# Nixie.net
KiCad netlist of a schematic drawn in EAGLE
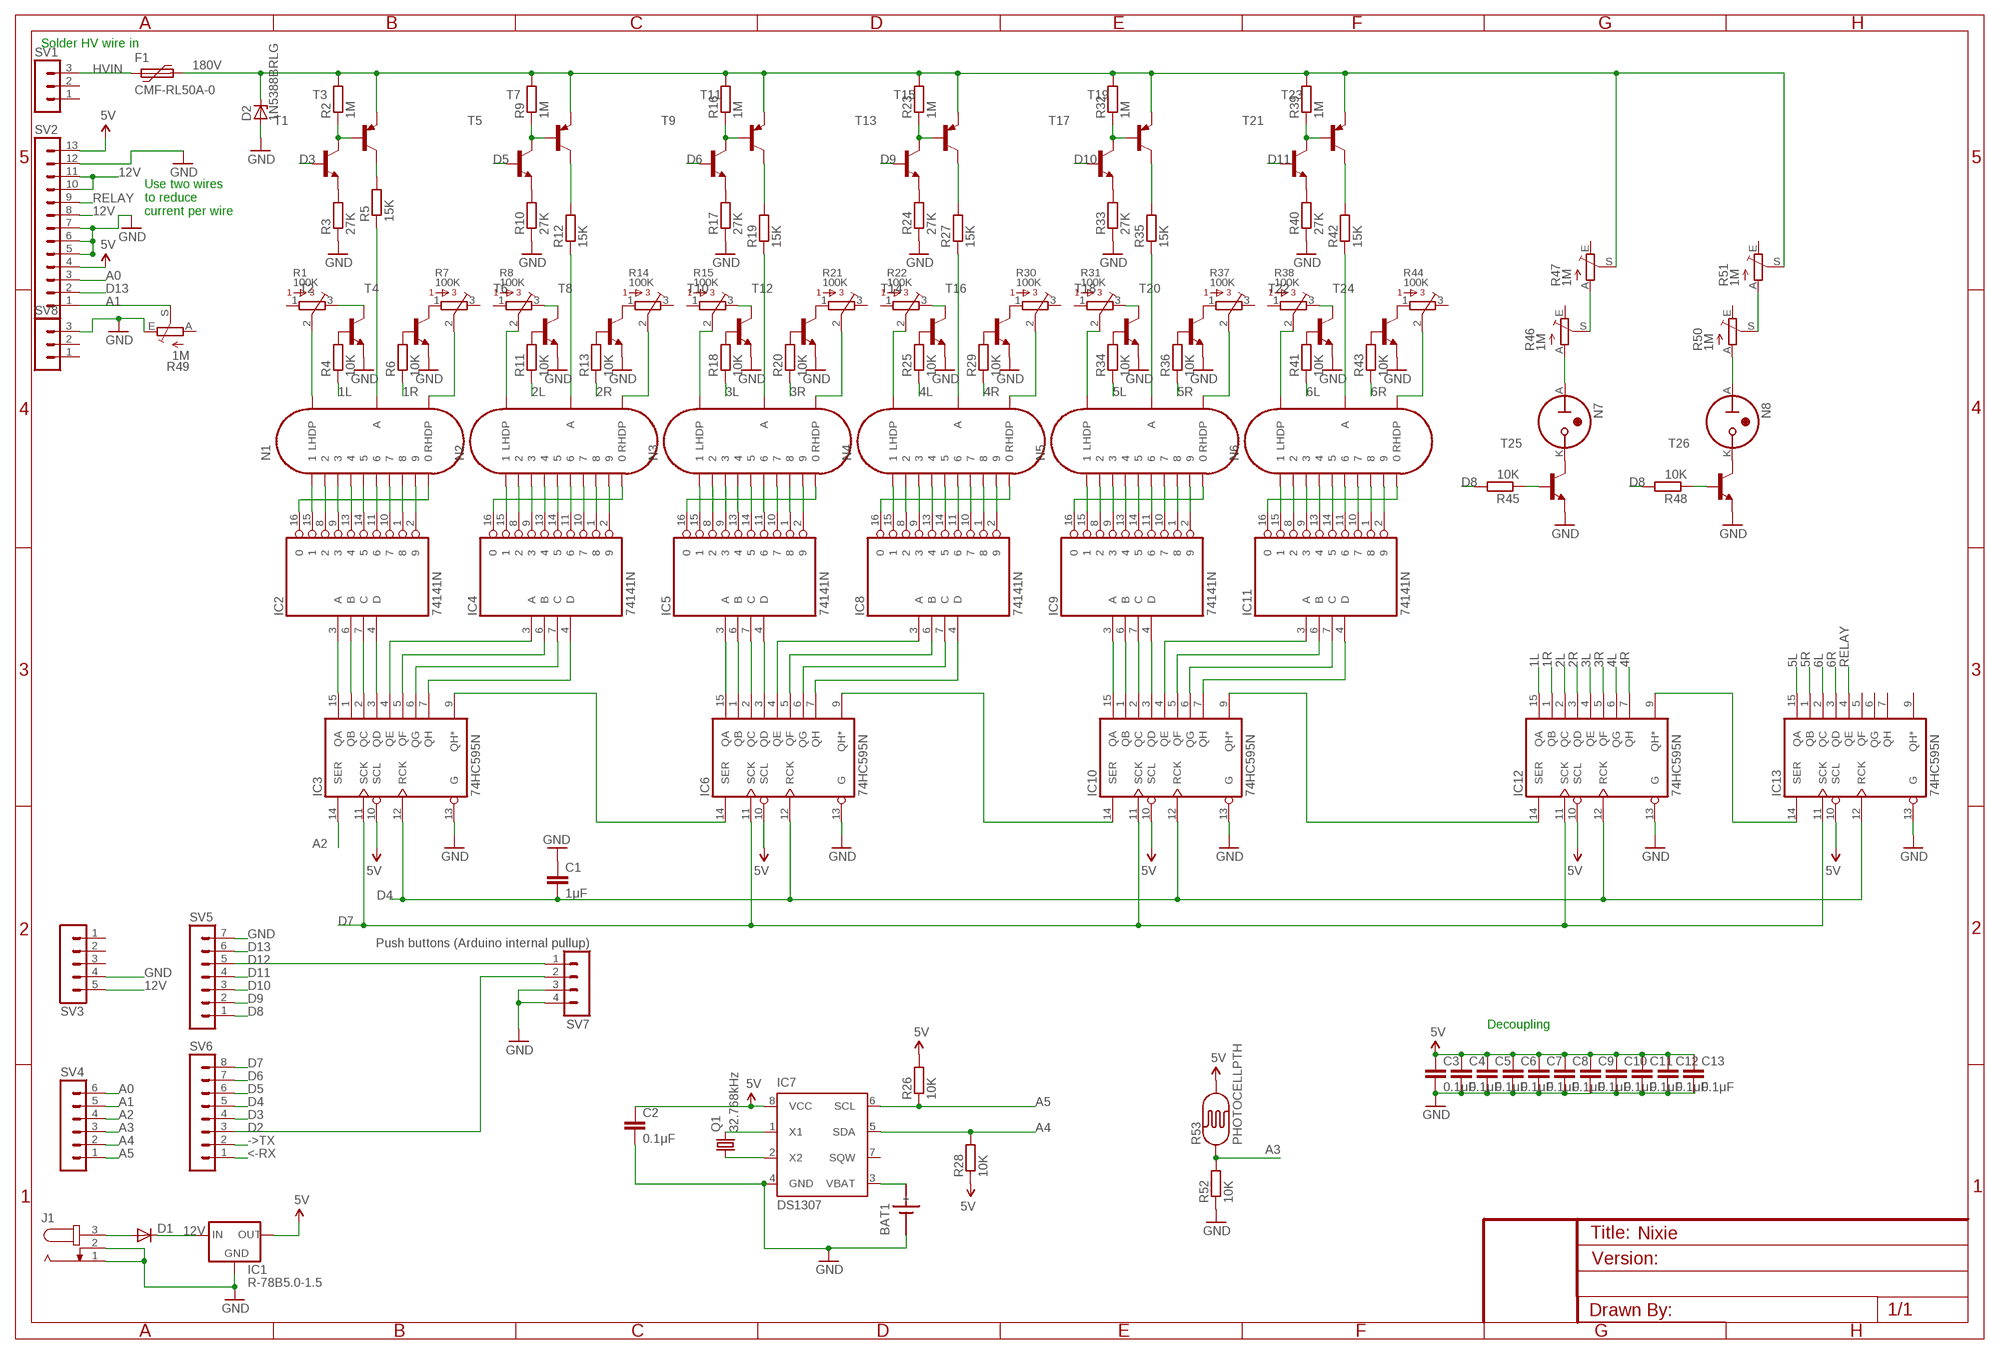
[diagram p0: schematic, sheet 1]

(export (version "E")
  (design (tool "Eeschema 10.0.6"))
  (components
    (comp (ref "BAT1")
      (value "SN2032")
      (footprint "eagle-import:SN2032")
      (libsource (lib "eagle-import") (part "SN2032"))
    )
    (comp (ref "C1")
      (value "1μF")
      (footprint "eagle-import:C2.5-2")
      (libsource (lib "eagle-import") (part "C2.5/2"))
    )
    (comp (ref "C2")
      (value "0.1μF")
      (footprint "eagle-import:C2.5-2")
      (libsource (lib "eagle-import") (part "C2.5/2"))
    )
    (comp (ref "C3")
      (value "0.1μF")
      (footprint "eagle-import:C2.5-2")
      (libsource (lib "eagle-import") (part "C2.5/2"))
    )
    (comp (ref "C4")
      (value "0.1μF")
      (footprint "eagle-import:C2.5-2")
      (libsource (lib "eagle-import") (part "C2.5/2"))
    )
    (comp (ref "C5")
      (value "0.1μF")
      (footprint "eagle-import:C2.5-2")
      (libsource (lib "eagle-import") (part "C2.5/2"))
    )
    (comp (ref "C6")
      (value "0.1μF")
      (footprint "eagle-import:C2.5-2")
      (libsource (lib "eagle-import") (part "C2.5/2"))
    )
    (comp (ref "C7")
      (value "0.1μF")
      (footprint "eagle-import:C2.5-2")
      (libsource (lib "eagle-import") (part "C2.5/2"))
    )
    (comp (ref "C8")
      (value "0.1μF")
      (footprint "eagle-import:C2.5-2")
      (libsource (lib "eagle-import") (part "C2.5/2"))
    )
    (comp (ref "C9")
      (value "0.1μF")
      (footprint "eagle-import:C2.5-2")
      (libsource (lib "eagle-import") (part "C2.5/2"))
    )
    (comp (ref "C10")
      (value "0.1μF")
      (footprint "eagle-import:C2.5-2")
      (libsource (lib "eagle-import") (part "C2.5/2"))
    )
    (comp (ref "C11")
      (value "0.1μF")
      (footprint "eagle-import:C2.5-2")
      (libsource (lib "eagle-import") (part "C2.5/2"))
    )
    (comp (ref "C12")
      (value "0.1μF")
      (footprint "eagle-import:C2.5-2")
      (libsource (lib "eagle-import") (part "C2.5/2"))
    )
    (comp (ref "C13")
      (value "0.1μF")
      (footprint "eagle-import:C2.5-2")
      (libsource (lib "eagle-import") (part "C2.5/2"))
    )
    (comp (ref "D1")
      (value "1N5400")
      (footprint "eagle-import:DO201-15")
      (libsource (lib "eagle-import") (part "1N5400"))
    )
    (comp (ref "D2")
      (value "1N5388BRLG")
      (footprint "eagle-import:C1702-15")
      (libsource (lib "eagle-import") (part "1N5333"))
    )
    (comp (ref "F1")
      (value "CMF-RL50A-0")
      (footprint "eagle-import:MF-5,1")
      (libsource (lib "eagle-import") (part "MF-R055-5,1"))
    )
    (comp (ref "IC1")
      (value "R-78B5.0-1.5")
      (footprint "eagle-import:SIP3V")
      (fields (field (name "MF") "Recom"))
      (libsource (lib "eagle-import") (part "R-78B-1.55.0"))
    )
    (comp (ref "IC2")
      (value "74141N")
      (footprint "eagle-import:DIL16")
      (libsource (lib "eagle-import") (part "74141N"))
    )
    (comp (ref "IC3")
      (value "74HC595N")
      (footprint "eagle-import:DIL16")
      (libsource (lib "eagle-import") (part "74595NHC"))
    )
    (comp (ref "IC4")
      (value "74141N")
      (footprint "eagle-import:DIL16")
      (libsource (lib "eagle-import") (part "74141N"))
    )
    (comp (ref "IC5")
      (value "74141N")
      (footprint "eagle-import:DIL16")
      (libsource (lib "eagle-import") (part "74141N"))
    )
    (comp (ref "IC6")
      (value "74HC595N")
      (footprint "eagle-import:DIL16")
      (libsource (lib "eagle-import") (part "74595NHC"))
    )
    (comp (ref "IC7")
      (value "DS1307")
      (footprint "eagle-import:DIL08")
      (libsource (lib "eagle-import") (part "DS1307"))
    )
    (comp (ref "IC8")
      (value "74141N")
      (footprint "eagle-import:DIL16")
      (libsource (lib "eagle-import") (part "74141N"))
    )
    (comp (ref "IC9")
      (value "74141N")
      (footprint "eagle-import:DIL16")
      (libsource (lib "eagle-import") (part "74141N"))
    )
    (comp (ref "IC10")
      (value "74HC595N")
      (footprint "eagle-import:DIL16")
      (libsource (lib "eagle-import") (part "74595NHC"))
    )
    (comp (ref "IC11")
      (value "74141N")
      (footprint "eagle-import:DIL16")
      (libsource (lib "eagle-import") (part "74141N"))
    )
    (comp (ref "IC12")
      (value "74HC595N")
      (footprint "eagle-import:DIL16")
      (libsource (lib "eagle-import") (part "74595NHC"))
    )
    (comp (ref "IC13")
      (value "74HC595N")
      (footprint "eagle-import:DIL16")
      (libsource (lib "eagle-import") (part "74595NHC"))
    )
    (comp (ref "J1")
      (value "JACK-PLUG0")
      (footprint "eagle-import:SPC4077")
      (libsource (lib "eagle-import") (part "JACK-PLUG0"))
    )
    (comp (ref "N1")
      (value "IN-14")
      (footprint "eagle-import:IN-14")
      (libsource (lib "eagle-import") (part "IN-14"))
    )
    (comp (ref "N2")
      (value "IN-14")
      (footprint "eagle-import:IN-14")
      (libsource (lib "eagle-import") (part "IN-14"))
    )
    (comp (ref "N3")
      (value "IN-14")
      (footprint "eagle-import:IN-14")
      (libsource (lib "eagle-import") (part "IN-14"))
    )
    (comp (ref "N4")
      (value "IN-14")
      (footprint "eagle-import:IN-14")
      (libsource (lib "eagle-import") (part "IN-14"))
    )
    (comp (ref "N5")
      (value "IN-14")
      (footprint "eagle-import:IN-14")
      (libsource (lib "eagle-import") (part "IN-14"))
    )
    (comp (ref "N6")
      (value "IN-14")
      (footprint "eagle-import:IN-14")
      (libsource (lib "eagle-import") (part "IN-14"))
    )
    (comp (ref "N7")
      (value "IN-3")
      (footprint "eagle-import:IN-3")
      (libsource (lib "eagle-import") (part "IN-3"))
    )
    (comp (ref "N8")
      (value "IN-3")
      (footprint "eagle-import:IN-3")
      (libsource (lib "eagle-import") (part "IN-3"))
    )
    (comp (ref "Q1")
      (value "32.768kHz")
      (footprint "eagle-import:TC26V")
      (libsource (lib "eagle-import") (part "CRYSTALTC26V"))
    )
    (comp (ref "R1")
      (value "100K")
      (footprint "eagle-import:3362P")
      (libsource (lib "eagle-import") (part "3362P"))
    )
    (comp (ref "R2")
      (value "1M")
      (footprint "eagle-import:0207_10")
      (libsource (lib "eagle-import") (part "R-EU_0207/10"))
    )
    (comp (ref "R3")
      (value "27K")
      (footprint "eagle-import:0207_10")
      (libsource (lib "eagle-import") (part "R-EU_0207/10"))
    )
    (comp (ref "R4")
      (value "10K")
      (footprint "eagle-import:0207_10")
      (libsource (lib "eagle-import") (part "R-EU_0207/10"))
    )
    (comp (ref "R5")
      (value "15K")
      (footprint "eagle-import:0207_10")
      (libsource (lib "eagle-import") (part "R-EU_0207/10"))
    )
    (comp (ref "R6")
      (value "10K")
      (footprint "eagle-import:0207_10")
      (libsource (lib "eagle-import") (part "R-EU_0207/10"))
    )
    (comp (ref "R7")
      (value "100K")
      (footprint "eagle-import:3362P")
      (libsource (lib "eagle-import") (part "3362P"))
    )
    (comp (ref "R8")
      (value "100K")
      (footprint "eagle-import:3362P")
      (libsource (lib "eagle-import") (part "3362P"))
    )
    (comp (ref "R9")
      (value "1M")
      (footprint "eagle-import:0207_10")
      (libsource (lib "eagle-import") (part "R-EU_0207/10"))
    )
    (comp (ref "R10")
      (value "27K")
      (footprint "eagle-import:0207_10")
      (libsource (lib "eagle-import") (part "R-EU_0207/10"))
    )
    (comp (ref "R11")
      (value "10K")
      (footprint "eagle-import:0207_10")
      (libsource (lib "eagle-import") (part "R-EU_0207/10"))
    )
    (comp (ref "R12")
      (value "15K")
      (footprint "eagle-import:0207_10")
      (libsource (lib "eagle-import") (part "R-EU_0207/10"))
    )
    (comp (ref "R13")
      (value "10K")
      (footprint "eagle-import:0207_10")
      (libsource (lib "eagle-import") (part "R-EU_0207/10"))
    )
    (comp (ref "R14")
      (value "100K")
      (footprint "eagle-import:3362P")
      (libsource (lib "eagle-import") (part "3362P"))
    )
    (comp (ref "R15")
      (value "100K")
      (footprint "eagle-import:3362P")
      (libsource (lib "eagle-import") (part "3362P"))
    )
    (comp (ref "R16")
      (value "1M")
      (footprint "eagle-import:0207_10")
      (libsource (lib "eagle-import") (part "R-EU_0207/10"))
    )
    (comp (ref "R17")
      (value "27K")
      (footprint "eagle-import:0207_10")
      (libsource (lib "eagle-import") (part "R-EU_0207/10"))
    )
    (comp (ref "R18")
      (value "10K")
      (footprint "eagle-import:0207_10")
      (libsource (lib "eagle-import") (part "R-EU_0207/10"))
    )
    (comp (ref "R19")
      (value "15K")
      (footprint "eagle-import:0207_10")
      (libsource (lib "eagle-import") (part "R-EU_0207/10"))
    )
    (comp (ref "R20")
      (value "10K")
      (footprint "eagle-import:0207_10")
      (libsource (lib "eagle-import") (part "R-EU_0207/10"))
    )
    (comp (ref "R21")
      (value "100K")
      (footprint "eagle-import:3362P")
      (libsource (lib "eagle-import") (part "3362P"))
    )
    (comp (ref "R22")
      (value "100K")
      (footprint "eagle-import:3362P")
      (libsource (lib "eagle-import") (part "3362P"))
    )
    (comp (ref "R23")
      (value "1M")
      (footprint "eagle-import:0207_10")
      (libsource (lib "eagle-import") (part "R-EU_0207/10"))
    )
    (comp (ref "R24")
      (value "27K")
      (footprint "eagle-import:0207_10")
      (libsource (lib "eagle-import") (part "R-EU_0207/10"))
    )
    (comp (ref "R25")
      (value "10K")
      (footprint "eagle-import:0207_10")
      (libsource (lib "eagle-import") (part "R-EU_0207/10"))
    )
    (comp (ref "R26")
      (value "10K")
      (footprint "eagle-import:0207_10")
      (libsource (lib "eagle-import") (part "R-EU_0207/10"))
    )
    (comp (ref "R27")
      (value "15K")
      (footprint "eagle-import:0207_10")
      (libsource (lib "eagle-import") (part "R-EU_0207/10"))
    )
    (comp (ref "R28")
      (value "10K")
      (footprint "eagle-import:0207_10")
      (libsource (lib "eagle-import") (part "R-EU_0207/10"))
    )
    (comp (ref "R29")
      (value "10K")
      (footprint "eagle-import:0207_10")
      (libsource (lib "eagle-import") (part "R-EU_0207/10"))
    )
    (comp (ref "R30")
      (value "100K")
      (footprint "eagle-import:3362P")
      (libsource (lib "eagle-import") (part "3362P"))
    )
    (comp (ref "R31")
      (value "100K")
      (footprint "eagle-import:3362P")
      (libsource (lib "eagle-import") (part "3362P"))
    )
    (comp (ref "R32")
      (value "1M")
      (footprint "eagle-import:0207_10")
      (libsource (lib "eagle-import") (part "R-EU_0207/10"))
    )
    (comp (ref "R33")
      (value "27K")
      (footprint "eagle-import:0207_10")
      (libsource (lib "eagle-import") (part "R-EU_0207/10"))
    )
    (comp (ref "R34")
      (value "10K")
      (footprint "eagle-import:0207_10")
      (libsource (lib "eagle-import") (part "R-EU_0207/10"))
    )
    (comp (ref "R35")
      (value "15K")
      (footprint "eagle-import:0207_10")
      (libsource (lib "eagle-import") (part "R-EU_0207/10"))
    )
    (comp (ref "R36")
      (value "10K")
      (footprint "eagle-import:0207_10")
      (libsource (lib "eagle-import") (part "R-EU_0207/10"))
    )
    (comp (ref "R37")
      (value "100K")
      (footprint "eagle-import:3362P")
      (libsource (lib "eagle-import") (part "3362P"))
    )
    (comp (ref "R38")
      (value "100K")
      (footprint "eagle-import:3362P")
      (libsource (lib "eagle-import") (part "3362P"))
    )
    (comp (ref "R39")
      (value "1M")
      (footprint "eagle-import:0207_10")
      (libsource (lib "eagle-import") (part "R-EU_0207/10"))
    )
    (comp (ref "R40")
      (value "27K")
      (footprint "eagle-import:0207_10")
      (libsource (lib "eagle-import") (part "R-EU_0207/10"))
    )
    (comp (ref "R41")
      (value "10K")
      (footprint "eagle-import:0207_10")
      (libsource (lib "eagle-import") (part "R-EU_0207/10"))
    )
    (comp (ref "R42")
      (value "15K")
      (footprint "eagle-import:0207_10")
      (libsource (lib "eagle-import") (part "R-EU_0207/10"))
    )
    (comp (ref "R43")
      (value "10K")
      (footprint "eagle-import:0207_10")
      (libsource (lib "eagle-import") (part "R-EU_0207/10"))
    )
    (comp (ref "R44")
      (value "100K")
      (footprint "eagle-import:3362P")
      (libsource (lib "eagle-import") (part "3362P"))
    )
    (comp (ref "R45")
      (value "10K")
      (footprint "eagle-import:0207_10")
      (libsource (lib "eagle-import") (part "R-EU_0207/10"))
    )
    (comp (ref "R46")
      (value "1M")
      (footprint "eagle-import:ECP10S")
      (libsource (lib "eagle-import") (part "TRIM_EU-ECP10S"))
    )
    (comp (ref "R47")
      (value "1M")
      (footprint "eagle-import:ECP10S")
      (libsource (lib "eagle-import") (part "TRIM_EU-ECP10S"))
    )
    (comp (ref "R48")
      (value "10K")
      (footprint "eagle-import:0207_10")
      (libsource (lib "eagle-import") (part "R-EU_0207/10"))
    )
    (comp (ref "R49")
      (value "1M")
      (footprint "eagle-import:ECP10S")
      (libsource (lib "eagle-import") (part "TRIM_EU-ECP10S"))
    )
    (comp (ref "R50")
      (value "1M")
      (footprint "eagle-import:ECP10S")
      (libsource (lib "eagle-import") (part "TRIM_EU-ECP10S"))
    )
    (comp (ref "R51")
      (value "1M")
      (footprint "eagle-import:ECP10S")
      (libsource (lib "eagle-import") (part "TRIM_EU-ECP10S"))
    )
    (comp (ref "R52")
      (value "10K")
      (footprint "eagle-import:0207_10")
      (libsource (lib "eagle-import") (part "R-EU_0207/10"))
    )
    (comp (ref "R53")
      (value "PHOTOCELLPTH")
      (footprint "eagle-import:PHOTOCELL")
      (libsource (lib "eagle-import") (part "PHOTOCELLPTH"))
    )
    (comp (ref "SV1")
      (value "MA03-1")
      (footprint "eagle-import:MA03-1")
      (libsource (lib "eagle-import") (part "MA03-1"))
    )
    (comp (ref "SV2")
      (value "MA13-1")
      (footprint "eagle-import:MA13-1")
      (libsource (lib "eagle-import") (part "MA13-1"))
    )
    (comp (ref "SV3")
      (value "MA05-1")
      (footprint "eagle-import:MA05-1")
      (libsource (lib "eagle-import") (part "MA05-1"))
    )
    (comp (ref "SV4")
      (value "MA06-1")
      (footprint "eagle-import:MA06-1")
      (libsource (lib "eagle-import") (part "MA06-1"))
    )
    (comp (ref "SV5")
      (value "MA07-1")
      (footprint "eagle-import:MA07-1")
      (libsource (lib "eagle-import") (part "MA07-1"))
    )
    (comp (ref "SV6")
      (value "MA08-1")
      (footprint "eagle-import:MA08-1")
      (libsource (lib "eagle-import") (part "MA08-1"))
    )
    (comp (ref "SV7")
      (value "Push buttons (Arduino internal pullup)")
      (footprint "eagle-import:MA04-1")
      (libsource (lib "eagle-import") (part "MA04-1"))
    )
    (comp (ref "SV8")
      (value "MA03-1")
      (footprint "eagle-import:MA03-1")
      (fields (field (name "OC_FARNELL") "unknown") (field (name "OC_NEWARK") "unknown"))
      (libsource (lib "eagle-import") (part "MA03-1"))
    )
    (comp (ref "T1")
      (value "MPSA42-NPN-TO92-CBE")
      (footprint "eagle-import:TO92-CBE")
      (libsource (lib "eagle-import") (part "-NPN-TO92-CBEMPSA42"))
    )
    (comp (ref "T2")
      (value "MPSA42-NPN-TO92-CBE")
      (footprint "eagle-import:TO92-CBE")
      (libsource (lib "eagle-import") (part "-NPN-TO92-CBEMPSA42"))
    )
    (comp (ref "T3")
      (value "BC327-16-PNP-TO92-EBC")
      (footprint "eagle-import:TO92-EBC")
      (libsource (lib "eagle-import") (part "-PNP-TO92-EBCBC327-16"))
    )
    (comp (ref "T4")
      (value "MPSA42-NPN-TO92-CBE")
      (footprint "eagle-import:TO92-CBE")
      (libsource (lib "eagle-import") (part "-NPN-TO92-CBEMPSA42"))
    )
    (comp (ref "T5")
      (value "MPSA42-NPN-TO92-CBE")
      (footprint "eagle-import:TO92-CBE")
      (libsource (lib "eagle-import") (part "-NPN-TO92-CBEMPSA42"))
    )
    (comp (ref "T6")
      (value "MPSA42-NPN-TO92-CBE")
      (footprint "eagle-import:TO92-CBE")
      (libsource (lib "eagle-import") (part "-NPN-TO92-CBEMPSA42"))
    )
    (comp (ref "T7")
      (value "BC327-16-PNP-TO92-EBC")
      (footprint "eagle-import:TO92-EBC")
      (libsource (lib "eagle-import") (part "-PNP-TO92-EBCBC327-16"))
    )
    (comp (ref "T8")
      (value "MPSA42-NPN-TO92-CBE")
      (footprint "eagle-import:TO92-CBE")
      (libsource (lib "eagle-import") (part "-NPN-TO92-CBEMPSA42"))
    )
    (comp (ref "T9")
      (value "MPSA42-NPN-TO92-CBE")
      (footprint "eagle-import:TO92-CBE")
      (libsource (lib "eagle-import") (part "-NPN-TO92-CBEMPSA42"))
    )
    (comp (ref "T10")
      (value "MPSA42-NPN-TO92-CBE")
      (footprint "eagle-import:TO92-CBE")
      (libsource (lib "eagle-import") (part "-NPN-TO92-CBEMPSA42"))
    )
    (comp (ref "T11")
      (value "BC327-16-PNP-TO92-EBC")
      (footprint "eagle-import:TO92-EBC")
      (libsource (lib "eagle-import") (part "-PNP-TO92-EBCBC327-16"))
    )
    (comp (ref "T12")
      (value "MPSA42-NPN-TO92-CBE")
      (footprint "eagle-import:TO92-CBE")
      (libsource (lib "eagle-import") (part "-NPN-TO92-CBEMPSA42"))
    )
    (comp (ref "T13")
      (value "MPSA42-NPN-TO92-CBE")
      (footprint "eagle-import:TO92-CBE")
      (libsource (lib "eagle-import") (part "-NPN-TO92-CBEMPSA42"))
    )
    (comp (ref "T14")
      (value "MPSA42-NPN-TO92-CBE")
      (footprint "eagle-import:TO92-CBE")
      (libsource (lib "eagle-import") (part "-NPN-TO92-CBEMPSA42"))
    )
    (comp (ref "T15")
      (value "BC327-16-PNP-TO92-EBC")
      (footprint "eagle-import:TO92-EBC")
      (libsource (lib "eagle-import") (part "-PNP-TO92-EBCBC327-16"))
    )
    (comp (ref "T16")
      (value "MPSA42-NPN-TO92-CBE")
      (footprint "eagle-import:TO92-CBE")
      (libsource (lib "eagle-import") (part "-NPN-TO92-CBEMPSA42"))
    )
    (comp (ref "T17")
      (value "MPSA42-NPN-TO92-CBE")
      (footprint "eagle-import:TO92-CBE")
      (libsource (lib "eagle-import") (part "-NPN-TO92-CBEMPSA42"))
    )
    (comp (ref "T18")
      (value "MPSA42-NPN-TO92-CBE")
      (footprint "eagle-import:TO92-CBE")
      (libsource (lib "eagle-import") (part "-NPN-TO92-CBEMPSA42"))
    )
    (comp (ref "T19")
      (value "BC327-16-PNP-TO92-EBC")
      (footprint "eagle-import:TO92-EBC")
      (libsource (lib "eagle-import") (part "-PNP-TO92-EBCBC327-16"))
    )
    (comp (ref "T20")
      (value "MPSA42-NPN-TO92-CBE")
      (footprint "eagle-import:TO92-CBE")
      (libsource (lib "eagle-import") (part "-NPN-TO92-CBEMPSA42"))
    )
    (comp (ref "T21")
      (value "MPSA42-NPN-TO92-CBE")
      (footprint "eagle-import:TO92-CBE")
      (libsource (lib "eagle-import") (part "-NPN-TO92-CBEMPSA42"))
    )
    (comp (ref "T22")
      (value "MPSA42-NPN-TO92-CBE")
      (footprint "eagle-import:TO92-CBE")
      (libsource (lib "eagle-import") (part "-NPN-TO92-CBEMPSA42"))
    )
    (comp (ref "T23")
      (value "BC327-16-PNP-TO92-EBC")
      (footprint "eagle-import:TO92-EBC")
      (libsource (lib "eagle-import") (part "-PNP-TO92-EBCBC327-16"))
    )
    (comp (ref "T24")
      (value "MPSA42-NPN-TO92-CBE")
      (footprint "eagle-import:TO92-CBE")
      (libsource (lib "eagle-import") (part "-NPN-TO92-CBEMPSA42"))
    )
    (comp (ref "T25")
      (value "MPSA42-NPN-TO92-CBE")
      (footprint "eagle-import:TO92-CBE")
      (libsource (lib "eagle-import") (part "-NPN-TO92-CBEMPSA42"))
    )
    (comp (ref "T26")
      (value "MPSA42-NPN-TO92-CBE")
      (footprint "eagle-import:TO92-CBE")
      (libsource (lib "eagle-import") (part "-NPN-TO92-CBEMPSA42"))
    )
  )
  (nets
    (net (code "1") (name "/->TX") (class "Default")
      (node (ref "SV6") (pin "2") (pinfunction "2_2") (pintype "passive"))
    )
    (net (code "2") (name "/1L") (class "Default")
      (node (ref "IC12") (pin "15") (pinfunction "QA_15") (pintype "tri_state"))
      (node (ref "R4") (pin "1") (pinfunction "1_1") (pintype "passive"))
    )
    (net (code "3") (name "/1R") (class "Default")
      (node (ref "IC12") (pin "1") (pinfunction "QB_1") (pintype "tri_state"))
      (node (ref "R6") (pin "1") (pinfunction "1_1") (pintype "passive"))
    )
    (net (code "4") (name "/2L") (class "Default")
      (node (ref "IC12") (pin "2") (pinfunction "QC_2") (pintype "tri_state"))
      (node (ref "R11") (pin "1") (pinfunction "1_1") (pintype "passive"))
    )
    (net (code "5") (name "/2R") (class "Default")
      (node (ref "IC12") (pin "3") (pinfunction "QD_3") (pintype "tri_state"))
      (node (ref "R13") (pin "1") (pinfunction "1_1") (pintype "passive"))
    )
    (net (code "6") (name "/3L") (class "Default")
      (node (ref "IC12") (pin "4") (pinfunction "QE_4") (pintype "tri_state"))
      (node (ref "R18") (pin "1") (pinfunction "1_1") (pintype "passive"))
    )
    (net (code "7") (name "/3R") (class "Default")
      (node (ref "IC12") (pin "5") (pinfunction "QF_5") (pintype "tri_state"))
      (node (ref "R20") (pin "1") (pinfunction "1_1") (pintype "passive"))
    )
    (net (code "8") (name "/4L") (class "Default")
      (node (ref "IC12") (pin "6") (pinfunction "QG_6") (pintype "tri_state"))
      (node (ref "R25") (pin "1") (pinfunction "1_1") (pintype "passive"))
    )
    (net (code "9") (name "/4R") (class "Default")
      (node (ref "IC12") (pin "7") (pinfunction "QH_7") (pintype "tri_state"))
      (node (ref "R29") (pin "1") (pinfunction "1_1") (pintype "passive"))
    )
    (net (code "10") (name "/5L") (class "Default")
      (node (ref "IC13") (pin "15") (pinfunction "QA_15") (pintype "tri_state"))
      (node (ref "R34") (pin "1") (pinfunction "1_1") (pintype "passive"))
    )
    (net (code "11") (name "/5R") (class "Default")
      (node (ref "IC13") (pin "1") (pinfunction "QB_1") (pintype "tri_state"))
      (node (ref "R36") (pin "1") (pinfunction "1_1") (pintype "passive"))
    )
    (net (code "12") (name "/6L") (class "Default")
      (node (ref "IC13") (pin "2") (pinfunction "QC_2") (pintype "tri_state"))
      (node (ref "R41") (pin "1") (pinfunction "1_1") (pintype "passive"))
    )
    (net (code "13") (name "/6R") (class "Default")
      (node (ref "IC13") (pin "3") (pinfunction "QD_3") (pintype "tri_state"))
      (node (ref "R43") (pin "1") (pinfunction "1_1") (pintype "passive"))
    )
    (net (code "14") (name "/12V") (class "Default")
      (node (ref "D1") (pin "C") (pinfunction "C_C") (pintype "passive"))
      (node (ref "IC1") (pin "1") (pinfunction "IN_1") (pintype "input"))
      (node (ref "SV2") (pin "10") (pinfunction "10_10") (pintype "passive"))
      (node (ref "SV2") (pin "11") (pinfunction "11_11") (pintype "passive"))
      (node (ref "SV2") (pin "8") (pinfunction "8_8") (pintype "passive"))
      (node (ref "SV3") (pin "5") (pinfunction "5_5") (pintype "passive"))
    )
    (net (code "15") (name "/180V") (class "Default")
      (node (ref "D2") (pin "C") (pinfunction "C_C") (pintype "passive"))
      (node (ref "F1") (pin "2") (pinfunction "2_2") (pintype "passive"))
      (node (ref "R16") (pin "2") (pinfunction "2_2") (pintype "passive"))
      (node (ref "R2") (pin "2") (pinfunction "2_2") (pintype "passive"))
      (node (ref "R23") (pin "2") (pinfunction "2_2") (pintype "passive"))
      (node (ref "R32") (pin "2") (pinfunction "2_2") (pintype "passive"))
      (node (ref "R39") (pin "2") (pinfunction "2_2") (pintype "passive"))
      (node (ref "R47") (pin "S") (pinfunction "S_S") (pintype "passive"))
      (node (ref "R51") (pin "S") (pinfunction "S_S") (pintype "passive"))
      (node (ref "R9") (pin "2") (pinfunction "2_2") (pintype "passive"))
      (node (ref "T11") (pin "E") (pinfunction "E_E") (pintype "passive"))
      (node (ref "T15") (pin "E") (pinfunction "E_E") (pintype "passive"))
      (node (ref "T19") (pin "E") (pinfunction "E_E") (pintype "passive"))
      (node (ref "T23") (pin "E") (pinfunction "E_E") (pintype "passive"))
      (node (ref "T3") (pin "E") (pinfunction "E_E") (pintype "passive"))
      (node (ref "T7") (pin "E") (pinfunction "E_E") (pintype "passive"))
    )
    (net (code "16") (name "/<-RX") (class "Default")
      (node (ref "SV6") (pin "1") (pinfunction "1_1") (pintype "passive"))
    )
    (net (code "17") (name "/A0") (class "Default")
      (node (ref "SV2") (pin "3") (pinfunction "3_3") (pintype "passive"))
      (node (ref "SV4") (pin "6") (pinfunction "6_6") (pintype "passive"))
    )
    (net (code "18") (name "/A1") (class "Default")
      (node (ref "R49") (pin "S") (pinfunction "S_S") (pintype "passive"))
      (node (ref "SV2") (pin "1") (pinfunction "1_1") (pintype "passive"))
      (node (ref "SV4") (pin "5") (pinfunction "5_5") (pintype "passive"))
    )
    (net (code "19") (name "/A2") (class "Default")
      (node (ref "IC3") (pin "14") (pinfunction "SER_14") (pintype "input"))
      (node (ref "SV4") (pin "4") (pinfunction "4_4") (pintype "passive"))
    )
    (net (code "20") (name "/A3") (class "Default")
      (node (ref "R52") (pin "2") (pinfunction "2_2") (pintype "passive"))
      (node (ref "R53") (pin "1") (pinfunction "P$1_1") (pintype "bidirectional"))
      (node (ref "SV4") (pin "3") (pinfunction "3_3") (pintype "passive"))
    )
    (net (code "21") (name "/A4") (class "Default")
      (node (ref "IC7") (pin "5") (pinfunction "SDA_5") (pintype "bidirectional"))
      (node (ref "R28") (pin "2") (pinfunction "2_2") (pintype "passive"))
      (node (ref "SV4") (pin "2") (pinfunction "2_2") (pintype "passive"))
    )
    (net (code "22") (name "/A5") (class "Default")
      (node (ref "IC7") (pin "6") (pinfunction "SCL_6") (pintype "input"))
      (node (ref "R26") (pin "1") (pinfunction "1_1") (pintype "passive"))
      (node (ref "SV4") (pin "1") (pinfunction "1_1") (pintype "passive"))
    )
    (net (code "23") (name "/D2") (class "Default")
      (node (ref "SV6") (pin "3") (pinfunction "3_3") (pintype "passive"))
      (node (ref "SV7") (pin "2") (pinfunction "2_2") (pintype "passive"))
    )
    (net (code "24") (name "/D3") (class "Default")
      (node (ref "SV6") (pin "4") (pinfunction "4_4") (pintype "passive"))
      (node (ref "T1") (pin "B") (pinfunction "B_B") (pintype "passive"))
    )
    (net (code "25") (name "/D4") (class "Default")
      (node (ref "C1") (pin "2") (pinfunction "2_2") (pintype "passive"))
      (node (ref "IC10") (pin "12") (pinfunction "RCK_12") (pintype "input"))
      (node (ref "IC12") (pin "12") (pinfunction "RCK_12") (pintype "input"))
      (node (ref "IC13") (pin "12") (pinfunction "RCK_12") (pintype "input"))
      (node (ref "IC3") (pin "12") (pinfunction "RCK_12") (pintype "input"))
      (node (ref "IC6") (pin "12") (pinfunction "RCK_12") (pintype "input"))
      (node (ref "SV6") (pin "5") (pinfunction "5_5") (pintype "passive"))
    )
    (net (code "26") (name "/D5") (class "Default")
      (node (ref "SV6") (pin "6") (pinfunction "6_6") (pintype "passive"))
      (node (ref "T5") (pin "B") (pinfunction "B_B") (pintype "passive"))
    )
    (net (code "27") (name "/D6") (class "Default")
      (node (ref "SV6") (pin "7") (pinfunction "7_7") (pintype "passive"))
      (node (ref "T9") (pin "B") (pinfunction "B_B") (pintype "passive"))
    )
    (net (code "28") (name "/D7") (class "Default")
      (node (ref "IC10") (pin "11") (pinfunction "SCK_11") (pintype "input"))
      (node (ref "IC12") (pin "11") (pinfunction "SCK_11") (pintype "input"))
      (node (ref "IC13") (pin "11") (pinfunction "SCK_11") (pintype "input"))
      (node (ref "IC3") (pin "11") (pinfunction "SCK_11") (pintype "input"))
      (node (ref "IC6") (pin "11") (pinfunction "SCK_11") (pintype "input"))
      (node (ref "SV6") (pin "8") (pinfunction "8_8") (pintype "passive"))
    )
    (net (code "29") (name "/D8") (class "Default")
      (node (ref "R45") (pin "2") (pinfunction "2_2") (pintype "passive"))
      (node (ref "R48") (pin "2") (pinfunction "2_2") (pintype "passive"))
      (node (ref "SV5") (pin "1") (pinfunction "1_1") (pintype "passive"))
    )
    (net (code "30") (name "/D9") (class "Default")
      (node (ref "SV5") (pin "2") (pinfunction "2_2") (pintype "passive"))
      (node (ref "T13") (pin "B") (pinfunction "B_B") (pintype "passive"))
    )
    (net (code "31") (name "/D10") (class "Default")
      (node (ref "SV5") (pin "3") (pinfunction "3_3") (pintype "passive"))
      (node (ref "T17") (pin "B") (pinfunction "B_B") (pintype "passive"))
    )
    (net (code "32") (name "/D11") (class "Default")
      (node (ref "SV5") (pin "4") (pinfunction "4_4") (pintype "passive"))
      (node (ref "T21") (pin "B") (pinfunction "B_B") (pintype "passive"))
    )
    (net (code "33") (name "/D12") (class "Default")
      (node (ref "SV5") (pin "5") (pinfunction "5_5") (pintype "passive"))
      (node (ref "SV7") (pin "1") (pinfunction "1_1") (pintype "passive"))
    )
    (net (code "34") (name "/D13") (class "Default")
      (node (ref "SV2") (pin "2") (pinfunction "2_2") (pintype "passive"))
      (node (ref "SV5") (pin "6") (pinfunction "6_6") (pintype "passive"))
    )
    (net (code "35") (name "/HVIN") (class "Default")
      (node (ref "F1") (pin "1") (pinfunction "1_1") (pintype "passive"))
      (node (ref "SV1") (pin "3") (pinfunction "3_3") (pintype "passive"))
    )
    (net (code "36") (name "/RELAY") (class "Default")
      (node (ref "IC13") (pin "4") (pinfunction "QE_4") (pintype "tri_state"))
      (node (ref "SV2") (pin "9") (pinfunction "9_9") (pintype "passive"))
    )
    (net (code "37") (name "5V") (class "Default")
      (node (ref "C10") (pin "1") (pinfunction "1_1") (pintype "passive"))
      (node (ref "C11") (pin "1") (pinfunction "1_1") (pintype "passive"))
      (node (ref "C12") (pin "1") (pinfunction "1_1") (pintype "passive"))
      (node (ref "C13") (pin "1") (pinfunction "1_1") (pintype "passive"))
      (node (ref "C2") (pin "1") (pinfunction "1_1") (pintype "passive"))
      (node (ref "C3") (pin "1") (pinfunction "1_1") (pintype "passive"))
      (node (ref "C4") (pin "1") (pinfunction "1_1") (pintype "passive"))
      (node (ref "C5") (pin "1") (pinfunction "1_1") (pintype "passive"))
      (node (ref "C6") (pin "1") (pinfunction "1_1") (pintype "passive"))
      (node (ref "C7") (pin "1") (pinfunction "1_1") (pintype "passive"))
      (node (ref "C8") (pin "1") (pinfunction "1_1") (pintype "passive"))
      (node (ref "C9") (pin "1") (pinfunction "1_1") (pintype "passive"))
      (node (ref "IC1") (pin "3") (pinfunction "OUT_3") (pintype "passive"))
      (node (ref "IC10") (pin "10") (pinfunction "SCL_10") (pintype "input"))
      (node (ref "IC12") (pin "10") (pinfunction "SCL_10") (pintype "input"))
      (node (ref "IC13") (pin "10") (pinfunction "SCL_10") (pintype "input"))
      (node (ref "IC3") (pin "10") (pinfunction "SCL_10") (pintype "input"))
      (node (ref "IC6") (pin "10") (pinfunction "SCL_10") (pintype "input"))
      (node (ref "IC7") (pin "8") (pinfunction "VCC_8") (pintype "power_in"))
      (node (ref "R26") (pin "2") (pinfunction "2_2") (pintype "passive"))
      (node (ref "R28") (pin "1") (pinfunction "1_1") (pintype "passive"))
      (node (ref "R53") (pin "2") (pinfunction "P$2_2") (pintype "bidirectional"))
      (node (ref "SV2") (pin "13") (pinfunction "13_13") (pintype "passive"))
      (node (ref "SV2") (pin "4") (pinfunction "4_4") (pintype "passive"))
    )
    (net (code "38") (name "GND") (class "Default")
      (node (ref "BAT1") (pin "-") (pinfunction "-_-") (pintype "passive"))
      (node (ref "C1") (pin "1") (pinfunction "1_1") (pintype "passive"))
      (node (ref "C10") (pin "2") (pinfunction "2_2") (pintype "passive"))
      (node (ref "C11") (pin "2") (pinfunction "2_2") (pintype "passive"))
      (node (ref "C12") (pin "2") (pinfunction "2_2") (pintype "passive"))
      (node (ref "C13") (pin "2") (pinfunction "2_2") (pintype "passive"))
      (node (ref "C2") (pin "2") (pinfunction "2_2") (pintype "passive"))
      (node (ref "C3") (pin "2") (pinfunction "2_2") (pintype "passive"))
      (node (ref "C4") (pin "2") (pinfunction "2_2") (pintype "passive"))
      (node (ref "C5") (pin "2") (pinfunction "2_2") (pintype "passive"))
      (node (ref "C6") (pin "2") (pinfunction "2_2") (pintype "passive"))
      (node (ref "C7") (pin "2") (pinfunction "2_2") (pintype "passive"))
      (node (ref "C8") (pin "2") (pinfunction "2_2") (pintype "passive"))
      (node (ref "C9") (pin "2") (pinfunction "2_2") (pintype "passive"))
      (node (ref "D2") (pin "A") (pinfunction "A_A") (pintype "passive"))
      (node (ref "IC1") (pin "2") (pinfunction "GND_2") (pintype "input"))
      (node (ref "IC10") (pin "13") (pinfunction "G_13") (pintype "input"))
      (node (ref "IC12") (pin "13") (pinfunction "G_13") (pintype "input"))
      (node (ref "IC13") (pin "13") (pinfunction "G_13") (pintype "input"))
      (node (ref "IC3") (pin "13") (pinfunction "G_13") (pintype "input"))
      (node (ref "IC6") (pin "13") (pinfunction "G_13") (pintype "input"))
      (node (ref "IC7") (pin "4") (pinfunction "GND_4") (pintype "power_in"))
      (node (ref "J1") (pin "1") (pinfunction "1_1") (pintype "passive"))
      (node (ref "J1") (pin "2") (pinfunction "2_2") (pintype "passive"))
      (node (ref "R10") (pin "1") (pinfunction "1_1") (pintype "passive"))
      (node (ref "R17") (pin "1") (pinfunction "1_1") (pintype "passive"))
      (node (ref "R24") (pin "1") (pinfunction "1_1") (pintype "passive"))
      (node (ref "R3") (pin "1") (pinfunction "1_1") (pintype "passive"))
      (node (ref "R33") (pin "1") (pinfunction "1_1") (pintype "passive"))
      (node (ref "R40") (pin "1") (pinfunction "1_1") (pintype "passive"))
      (node (ref "R49") (pin "E") (pinfunction "E_E") (pintype "passive"))
      (node (ref "R52") (pin "1") (pinfunction "1_1") (pintype "passive"))
      (node (ref "SV2") (pin "12") (pinfunction "12_12") (pintype "passive"))
      (node (ref "SV2") (pin "5") (pinfunction "5_5") (pintype "passive"))
      (node (ref "SV2") (pin "6") (pinfunction "6_6") (pintype "passive"))
      (node (ref "SV2") (pin "7") (pinfunction "7_7") (pintype "passive"))
      (node (ref "SV3") (pin "4") (pinfunction "4_4") (pintype "passive"))
      (node (ref "SV5") (pin "7") (pinfunction "7_7") (pintype "passive"))
      (node (ref "SV7") (pin "3") (pinfunction "3_3") (pintype "passive"))
      (node (ref "SV7") (pin "4") (pinfunction "4_4") (pintype "passive"))
      (node (ref "SV8") (pin "3") (pinfunction "3_3") (pintype "passive"))
      (node (ref "T10") (pin "E") (pinfunction "E_E") (pintype "passive"))
      (node (ref "T12") (pin "E") (pinfunction "E_E") (pintype "passive"))
      (node (ref "T14") (pin "E") (pinfunction "E_E") (pintype "passive"))
      (node (ref "T16") (pin "E") (pinfunction "E_E") (pintype "passive"))
      (node (ref "T18") (pin "E") (pinfunction "E_E") (pintype "passive"))
      (node (ref "T2") (pin "E") (pinfunction "E_E") (pintype "passive"))
      (node (ref "T20") (pin "E") (pinfunction "E_E") (pintype "passive"))
      (node (ref "T22") (pin "E") (pinfunction "E_E") (pintype "passive"))
      (node (ref "T24") (pin "E") (pinfunction "E_E") (pintype "passive"))
      (node (ref "T25") (pin "E") (pinfunction "E_E") (pintype "passive"))
      (node (ref "T26") (pin "E") (pinfunction "E_E") (pintype "passive"))
      (node (ref "T4") (pin "E") (pinfunction "E_E") (pintype "passive"))
      (node (ref "T6") (pin "E") (pinfunction "E_E") (pintype "passive"))
      (node (ref "T8") (pin "E") (pinfunction "E_E") (pintype "passive"))
    )
    (net (code "39") (name "Net-(D1-PadA)") (class "Default")
      (node (ref "D1") (pin "A") (pinfunction "A_A") (pintype "passive"))
      (node (ref "J1") (pin "3") (pinfunction "3_3") (pintype "passive"))
    )
    (net (code "40") (name "Net-(IC2A-0)") (class "Default")
      (node (ref "IC2") (pin "16") (pinfunction "0_16") (pintype "open_collector"))
      (node (ref "N1") (pin "0") (pinfunction "0_0") (pintype "bidirectional"))
    )
    (net (code "41") (name "Net-(IC2A-1)") (class "Default")
      (node (ref "IC2") (pin "15") (pinfunction "1_15") (pintype "open_collector"))
      (node (ref "N1") (pin "1") (pinfunction "1_1") (pintype "bidirectional"))
    )
    (net (code "42") (name "Net-(IC2A-2)") (class "Default")
      (node (ref "IC2") (pin "8") (pinfunction "2_8") (pintype "open_collector"))
      (node (ref "N1") (pin "2") (pinfunction "2_2") (pintype "bidirectional"))
    )
    (net (code "43") (name "Net-(IC2A-3)") (class "Default")
      (node (ref "IC2") (pin "9") (pinfunction "3_9") (pintype "open_collector"))
      (node (ref "N1") (pin "3") (pinfunction "3_3") (pintype "bidirectional"))
    )
    (net (code "44") (name "Net-(IC2A-4)") (class "Default")
      (node (ref "IC2") (pin "13") (pinfunction "4_13") (pintype "open_collector"))
      (node (ref "N1") (pin "4") (pinfunction "4_4") (pintype "bidirectional"))
    )
    (net (code "45") (name "Net-(IC2A-5)") (class "Default")
      (node (ref "IC2") (pin "14") (pinfunction "5_14") (pintype "open_collector"))
      (node (ref "N1") (pin "5") (pinfunction "5_5") (pintype "bidirectional"))
    )
    (net (code "46") (name "Net-(IC2A-6)") (class "Default")
      (node (ref "IC2") (pin "11") (pinfunction "6_11") (pintype "open_collector"))
      (node (ref "N1") (pin "6") (pinfunction "6_6") (pintype "bidirectional"))
    )
    (net (code "47") (name "Net-(IC2A-7)") (class "Default")
      (node (ref "IC2") (pin "10") (pinfunction "7_10") (pintype "open_collector"))
      (node (ref "N1") (pin "7") (pinfunction "7_7") (pintype "bidirectional"))
    )
    (net (code "48") (name "Net-(IC2A-8)") (class "Default")
      (node (ref "IC2") (pin "1") (pinfunction "8_1") (pintype "open_collector"))
      (node (ref "N1") (pin "8") (pinfunction "8_8") (pintype "bidirectional"))
    )
    (net (code "49") (name "Net-(IC2A-9)") (class "Default")
      (node (ref "IC2") (pin "2") (pinfunction "9_2") (pintype "open_collector"))
      (node (ref "N1") (pin "9") (pinfunction "9_9") (pintype "bidirectional"))
    )
    (net (code "50") (name "Net-(IC2A-A)") (class "Default")
      (node (ref "IC2") (pin "3") (pinfunction "A_3") (pintype "input"))
      (node (ref "IC3") (pin "15") (pinfunction "QA_15") (pintype "tri_state"))
    )
    (net (code "51") (name "Net-(IC2A-B)") (class "Default")
      (node (ref "IC2") (pin "6") (pinfunction "B_6") (pintype "input"))
      (node (ref "IC3") (pin "1") (pinfunction "QB_1") (pintype "tri_state"))
    )
    (net (code "52") (name "Net-(IC2A-C)") (class "Default")
      (node (ref "IC2") (pin "7") (pinfunction "C_7") (pintype "input"))
      (node (ref "IC3") (pin "2") (pinfunction "QC_2") (pintype "tri_state"))
    )
    (net (code "53") (name "Net-(IC2A-D)") (class "Default")
      (node (ref "IC2") (pin "4") (pinfunction "D_4") (pintype "input"))
      (node (ref "IC3") (pin "3") (pinfunction "QD_3") (pintype "tri_state"))
    )
    (net (code "54") (name "Net-(IC3A-QE)") (class "Default")
      (node (ref "IC3") (pin "4") (pinfunction "QE_4") (pintype "tri_state"))
      (node (ref "IC4") (pin "3") (pinfunction "A_3") (pintype "input"))
    )
    (net (code "55") (name "Net-(IC3A-QF)") (class "Default")
      (node (ref "IC3") (pin "5") (pinfunction "QF_5") (pintype "tri_state"))
      (node (ref "IC4") (pin "6") (pinfunction "B_6") (pintype "input"))
    )
    (net (code "56") (name "Net-(IC3A-QG)") (class "Default")
      (node (ref "IC3") (pin "6") (pinfunction "QG_6") (pintype "tri_state"))
      (node (ref "IC4") (pin "7") (pinfunction "C_7") (pintype "input"))
    )
    (net (code "57") (name "Net-(IC3A-QH)") (class "Default")
      (node (ref "IC3") (pin "7") (pinfunction "QH_7") (pintype "tri_state"))
      (node (ref "IC4") (pin "4") (pinfunction "D_4") (pintype "input"))
    )
    (net (code "58") (name "Net-(IC3A-QH*)") (class "Default")
      (node (ref "IC3") (pin "9") (pinfunction "QH*_9") (pintype "tri_state"))
      (node (ref "IC6") (pin "14") (pinfunction "SER_14") (pintype "input"))
    )
    (net (code "59") (name "Net-(IC4A-0)") (class "Default")
      (node (ref "IC4") (pin "16") (pinfunction "0_16") (pintype "open_collector"))
      (node (ref "N2") (pin "0") (pinfunction "0_0") (pintype "bidirectional"))
    )
    (net (code "60") (name "Net-(IC4A-1)") (class "Default")
      (node (ref "IC4") (pin "15") (pinfunction "1_15") (pintype "open_collector"))
      (node (ref "N2") (pin "1") (pinfunction "1_1") (pintype "bidirectional"))
    )
    (net (code "61") (name "Net-(IC4A-2)") (class "Default")
      (node (ref "IC4") (pin "8") (pinfunction "2_8") (pintype "open_collector"))
      (node (ref "N2") (pin "2") (pinfunction "2_2") (pintype "bidirectional"))
    )
    (net (code "62") (name "Net-(IC4A-3)") (class "Default")
      (node (ref "IC4") (pin "9") (pinfunction "3_9") (pintype "open_collector"))
      (node (ref "N2") (pin "3") (pinfunction "3_3") (pintype "bidirectional"))
    )
    (net (code "63") (name "Net-(IC4A-4)") (class "Default")
      (node (ref "IC4") (pin "13") (pinfunction "4_13") (pintype "open_collector"))
      (node (ref "N2") (pin "4") (pinfunction "4_4") (pintype "bidirectional"))
    )
    (net (code "64") (name "Net-(IC4A-5)") (class "Default")
      (node (ref "IC4") (pin "14") (pinfunction "5_14") (pintype "open_collector"))
      (node (ref "N2") (pin "5") (pinfunction "5_5") (pintype "bidirectional"))
    )
    (net (code "65") (name "Net-(IC4A-6)") (class "Default")
      (node (ref "IC4") (pin "11") (pinfunction "6_11") (pintype "open_collector"))
      (node (ref "N2") (pin "6") (pinfunction "6_6") (pintype "bidirectional"))
    )
    (net (code "66") (name "Net-(IC4A-7)") (class "Default")
      (node (ref "IC4") (pin "10") (pinfunction "7_10") (pintype "open_collector"))
      (node (ref "N2") (pin "7") (pinfunction "7_7") (pintype "bidirectional"))
    )
    (net (code "67") (name "Net-(IC4A-8)") (class "Default")
      (node (ref "IC4") (pin "1") (pinfunction "8_1") (pintype "open_collector"))
      (node (ref "N2") (pin "8") (pinfunction "8_8") (pintype "bidirectional"))
    )
    (net (code "68") (name "Net-(IC4A-9)") (class "Default")
      (node (ref "IC4") (pin "2") (pinfunction "9_2") (pintype "open_collector"))
      (node (ref "N2") (pin "9") (pinfunction "9_9") (pintype "bidirectional"))
    )
    (net (code "69") (name "Net-(IC5A-0)") (class "Default")
      (node (ref "IC5") (pin "16") (pinfunction "0_16") (pintype "open_collector"))
      (node (ref "N3") (pin "0") (pinfunction "0_0") (pintype "bidirectional"))
    )
    (net (code "70") (name "Net-(IC5A-1)") (class "Default")
      (node (ref "IC5") (pin "15") (pinfunction "1_15") (pintype "open_collector"))
      (node (ref "N3") (pin "1") (pinfunction "1_1") (pintype "bidirectional"))
    )
    (net (code "71") (name "Net-(IC5A-2)") (class "Default")
      (node (ref "IC5") (pin "8") (pinfunction "2_8") (pintype "open_collector"))
      (node (ref "N3") (pin "2") (pinfunction "2_2") (pintype "bidirectional"))
    )
    (net (code "72") (name "Net-(IC5A-3)") (class "Default")
      (node (ref "IC5") (pin "9") (pinfunction "3_9") (pintype "open_collector"))
      (node (ref "N3") (pin "3") (pinfunction "3_3") (pintype "bidirectional"))
    )
    (net (code "73") (name "Net-(IC5A-4)") (class "Default")
      (node (ref "IC5") (pin "13") (pinfunction "4_13") (pintype "open_collector"))
      (node (ref "N3") (pin "4") (pinfunction "4_4") (pintype "bidirectional"))
    )
    (net (code "74") (name "Net-(IC5A-5)") (class "Default")
      (node (ref "IC5") (pin "14") (pinfunction "5_14") (pintype "open_collector"))
      (node (ref "N3") (pin "5") (pinfunction "5_5") (pintype "bidirectional"))
    )
    (net (code "75") (name "Net-(IC5A-6)") (class "Default")
      (node (ref "IC5") (pin "11") (pinfunction "6_11") (pintype "open_collector"))
      (node (ref "N3") (pin "6") (pinfunction "6_6") (pintype "bidirectional"))
    )
    (net (code "76") (name "Net-(IC5A-7)") (class "Default")
      (node (ref "IC5") (pin "10") (pinfunction "7_10") (pintype "open_collector"))
      (node (ref "N3") (pin "7") (pinfunction "7_7") (pintype "bidirectional"))
    )
    (net (code "77") (name "Net-(IC5A-8)") (class "Default")
      (node (ref "IC5") (pin "1") (pinfunction "8_1") (pintype "open_collector"))
      (node (ref "N3") (pin "8") (pinfunction "8_8") (pintype "bidirectional"))
    )
    (net (code "78") (name "Net-(IC5A-9)") (class "Default")
      (node (ref "IC5") (pin "2") (pinfunction "9_2") (pintype "open_collector"))
      (node (ref "N3") (pin "9") (pinfunction "9_9") (pintype "bidirectional"))
    )
    (net (code "79") (name "Net-(IC5A-A)") (class "Default")
      (node (ref "IC5") (pin "3") (pinfunction "A_3") (pintype "input"))
      (node (ref "IC6") (pin "15") (pinfunction "QA_15") (pintype "tri_state"))
    )
    (net (code "80") (name "Net-(IC5A-B)") (class "Default")
      (node (ref "IC5") (pin "6") (pinfunction "B_6") (pintype "input"))
      (node (ref "IC6") (pin "1") (pinfunction "QB_1") (pintype "tri_state"))
    )
    (net (code "81") (name "Net-(IC5A-C)") (class "Default")
      (node (ref "IC5") (pin "7") (pinfunction "C_7") (pintype "input"))
      (node (ref "IC6") (pin "2") (pinfunction "QC_2") (pintype "tri_state"))
    )
    (net (code "82") (name "Net-(IC5A-D)") (class "Default")
      (node (ref "IC5") (pin "4") (pinfunction "D_4") (pintype "input"))
      (node (ref "IC6") (pin "3") (pinfunction "QD_3") (pintype "tri_state"))
    )
    (net (code "83") (name "Net-(IC6A-QE)") (class "Default")
      (node (ref "IC6") (pin "4") (pinfunction "QE_4") (pintype "tri_state"))
      (node (ref "IC8") (pin "3") (pinfunction "A_3") (pintype "input"))
    )
    (net (code "84") (name "Net-(IC6A-QF)") (class "Default")
      (node (ref "IC6") (pin "5") (pinfunction "QF_5") (pintype "tri_state"))
      (node (ref "IC8") (pin "6") (pinfunction "B_6") (pintype "input"))
    )
    (net (code "85") (name "Net-(IC6A-QG)") (class "Default")
      (node (ref "IC6") (pin "6") (pinfunction "QG_6") (pintype "tri_state"))
      (node (ref "IC8") (pin "7") (pinfunction "C_7") (pintype "input"))
    )
    (net (code "86") (name "Net-(IC6A-QH)") (class "Default")
      (node (ref "IC6") (pin "7") (pinfunction "QH_7") (pintype "tri_state"))
      (node (ref "IC8") (pin "4") (pinfunction "D_4") (pintype "input"))
    )
    (net (code "87") (name "Net-(IC7-VBAT)") (class "Default")
      (node (ref "BAT1") (pin "+") (pinfunction "+_+") (pintype "passive"))
      (node (ref "IC7") (pin "3") (pinfunction "VBAT_3") (pintype "passive"))
    )
    (net (code "88") (name "Net-(IC7-X1)") (class "Default")
      (node (ref "IC7") (pin "1") (pinfunction "X1_1") (pintype "input"))
      (node (ref "Q1") (pin "2") (pinfunction "2_2") (pintype "passive"))
    )
    (net (code "89") (name "Net-(IC7-X2)") (class "Default")
      (node (ref "IC7") (pin "2") (pinfunction "X2_2") (pintype "output"))
      (node (ref "Q1") (pin "1") (pinfunction "1_1") (pintype "passive"))
    )
    (net (code "90") (name "Net-(IC8A-0)") (class "Default")
      (node (ref "IC8") (pin "16") (pinfunction "0_16") (pintype "open_collector"))
      (node (ref "N4") (pin "0") (pinfunction "0_0") (pintype "bidirectional"))
    )
    (net (code "91") (name "Net-(IC8A-1)") (class "Default")
      (node (ref "IC8") (pin "15") (pinfunction "1_15") (pintype "open_collector"))
      (node (ref "N4") (pin "1") (pinfunction "1_1") (pintype "bidirectional"))
    )
    (net (code "92") (name "Net-(IC8A-2)") (class "Default")
      (node (ref "IC8") (pin "8") (pinfunction "2_8") (pintype "open_collector"))
      (node (ref "N4") (pin "2") (pinfunction "2_2") (pintype "bidirectional"))
    )
    (net (code "93") (name "Net-(IC8A-3)") (class "Default")
      (node (ref "IC8") (pin "9") (pinfunction "3_9") (pintype "open_collector"))
      (node (ref "N4") (pin "3") (pinfunction "3_3") (pintype "bidirectional"))
    )
    (net (code "94") (name "Net-(IC8A-4)") (class "Default")
      (node (ref "IC8") (pin "13") (pinfunction "4_13") (pintype "open_collector"))
      (node (ref "N4") (pin "4") (pinfunction "4_4") (pintype "bidirectional"))
    )
    (net (code "95") (name "Net-(IC8A-5)") (class "Default")
      (node (ref "IC8") (pin "14") (pinfunction "5_14") (pintype "open_collector"))
      (node (ref "N4") (pin "5") (pinfunction "5_5") (pintype "bidirectional"))
    )
    (net (code "96") (name "Net-(IC8A-6)") (class "Default")
      (node (ref "IC8") (pin "11") (pinfunction "6_11") (pintype "open_collector"))
      (node (ref "N4") (pin "6") (pinfunction "6_6") (pintype "bidirectional"))
    )
    (net (code "97") (name "Net-(IC8A-7)") (class "Default")
      (node (ref "IC8") (pin "10") (pinfunction "7_10") (pintype "open_collector"))
      (node (ref "N4") (pin "7") (pinfunction "7_7") (pintype "bidirectional"))
    )
    (net (code "98") (name "Net-(IC8A-8)") (class "Default")
      (node (ref "IC8") (pin "1") (pinfunction "8_1") (pintype "open_collector"))
      (node (ref "N4") (pin "8") (pinfunction "8_8") (pintype "bidirectional"))
    )
    (net (code "99") (name "Net-(IC8A-9)") (class "Default")
      (node (ref "IC8") (pin "2") (pinfunction "9_2") (pintype "open_collector"))
      (node (ref "N4") (pin "9") (pinfunction "9_9") (pintype "bidirectional"))
    )
    (net (code "100") (name "Net-(IC9A-0)") (class "Default")
      (node (ref "IC9") (pin "16") (pinfunction "0_16") (pintype "open_collector"))
      (node (ref "N5") (pin "0") (pinfunction "0_0") (pintype "bidirectional"))
    )
    (net (code "101") (name "Net-(IC9A-1)") (class "Default")
      (node (ref "IC9") (pin "15") (pinfunction "1_15") (pintype "open_collector"))
      (node (ref "N5") (pin "1") (pinfunction "1_1") (pintype "bidirectional"))
    )
    (net (code "102") (name "Net-(IC9A-2)") (class "Default")
      (node (ref "IC9") (pin "8") (pinfunction "2_8") (pintype "open_collector"))
      (node (ref "N5") (pin "2") (pinfunction "2_2") (pintype "bidirectional"))
    )
    (net (code "103") (name "Net-(IC9A-3)") (class "Default")
      (node (ref "IC9") (pin "9") (pinfunction "3_9") (pintype "open_collector"))
      (node (ref "N5") (pin "3") (pinfunction "3_3") (pintype "bidirectional"))
    )
    (net (code "104") (name "Net-(IC9A-4)") (class "Default")
      (node (ref "IC9") (pin "13") (pinfunction "4_13") (pintype "open_collector"))
      (node (ref "N5") (pin "4") (pinfunction "4_4") (pintype "bidirectional"))
    )
    (net (code "105") (name "Net-(IC9A-5)") (class "Default")
      (node (ref "IC9") (pin "14") (pinfunction "5_14") (pintype "open_collector"))
      (node (ref "N5") (pin "5") (pinfunction "5_5") (pintype "bidirectional"))
    )
    (net (code "106") (name "Net-(IC9A-6)") (class "Default")
      (node (ref "IC9") (pin "11") (pinfunction "6_11") (pintype "open_collector"))
      (node (ref "N5") (pin "6") (pinfunction "6_6") (pintype "bidirectional"))
    )
    (net (code "107") (name "Net-(IC9A-7)") (class "Default")
      (node (ref "IC9") (pin "10") (pinfunction "7_10") (pintype "open_collector"))
      (node (ref "N5") (pin "7") (pinfunction "7_7") (pintype "bidirectional"))
    )
    (net (code "108") (name "Net-(IC9A-8)") (class "Default")
      (node (ref "IC9") (pin "1") (pinfunction "8_1") (pintype "open_collector"))
      (node (ref "N5") (pin "8") (pinfunction "8_8") (pintype "bidirectional"))
    )
    (net (code "109") (name "Net-(IC9A-9)") (class "Default")
      (node (ref "IC9") (pin "2") (pinfunction "9_2") (pintype "open_collector"))
      (node (ref "N5") (pin "9") (pinfunction "9_9") (pintype "bidirectional"))
    )
    (net (code "110") (name "Net-(IC10A-QA)") (class "Default")
      (node (ref "IC10") (pin "15") (pinfunction "QA_15") (pintype "tri_state"))
      (node (ref "IC9") (pin "3") (pinfunction "A_3") (pintype "input"))
    )
    (net (code "111") (name "Net-(IC10A-QB)") (class "Default")
      (node (ref "IC10") (pin "1") (pinfunction "QB_1") (pintype "tri_state"))
      (node (ref "IC9") (pin "6") (pinfunction "B_6") (pintype "input"))
    )
    (net (code "112") (name "Net-(IC10A-QC)") (class "Default")
      (node (ref "IC10") (pin "2") (pinfunction "QC_2") (pintype "tri_state"))
      (node (ref "IC9") (pin "7") (pinfunction "C_7") (pintype "input"))
    )
    (net (code "113") (name "Net-(IC10A-QD)") (class "Default")
      (node (ref "IC10") (pin "3") (pinfunction "QD_3") (pintype "tri_state"))
      (node (ref "IC9") (pin "4") (pinfunction "D_4") (pintype "input"))
    )
    (net (code "114") (name "Net-(IC10A-QE)") (class "Default")
      (node (ref "IC10") (pin "4") (pinfunction "QE_4") (pintype "tri_state"))
      (node (ref "IC11") (pin "3") (pinfunction "A_3") (pintype "input"))
    )
    (net (code "115") (name "Net-(IC10A-QF)") (class "Default")
      (node (ref "IC10") (pin "5") (pinfunction "QF_5") (pintype "tri_state"))
      (node (ref "IC11") (pin "6") (pinfunction "B_6") (pintype "input"))
    )
    (net (code "116") (name "Net-(IC10A-QG)") (class "Default")
      (node (ref "IC10") (pin "6") (pinfunction "QG_6") (pintype "tri_state"))
      (node (ref "IC11") (pin "7") (pinfunction "C_7") (pintype "input"))
    )
    (net (code "117") (name "Net-(IC10A-QH)") (class "Default")
      (node (ref "IC10") (pin "7") (pinfunction "QH_7") (pintype "tri_state"))
      (node (ref "IC11") (pin "4") (pinfunction "D_4") (pintype "input"))
    )
    (net (code "118") (name "Net-(IC10A-QH*)") (class "Default")
      (node (ref "IC10") (pin "9") (pinfunction "QH*_9") (pintype "tri_state"))
      (node (ref "IC12") (pin "14") (pinfunction "SER_14") (pintype "input"))
    )
    (net (code "119") (name "Net-(IC10A-SER)") (class "Default")
      (node (ref "IC10") (pin "14") (pinfunction "SER_14") (pintype "input"))
      (node (ref "IC6") (pin "9") (pinfunction "QH*_9") (pintype "tri_state"))
    )
    (net (code "120") (name "Net-(IC11A-0)") (class "Default")
      (node (ref "IC11") (pin "16") (pinfunction "0_16") (pintype "open_collector"))
      (node (ref "N6") (pin "0") (pinfunction "0_0") (pintype "bidirectional"))
    )
    (net (code "121") (name "Net-(IC11A-1)") (class "Default")
      (node (ref "IC11") (pin "15") (pinfunction "1_15") (pintype "open_collector"))
      (node (ref "N6") (pin "1") (pinfunction "1_1") (pintype "bidirectional"))
    )
    (net (code "122") (name "Net-(IC11A-2)") (class "Default")
      (node (ref "IC11") (pin "8") (pinfunction "2_8") (pintype "open_collector"))
      (node (ref "N6") (pin "2") (pinfunction "2_2") (pintype "bidirectional"))
    )
    (net (code "123") (name "Net-(IC11A-3)") (class "Default")
      (node (ref "IC11") (pin "9") (pinfunction "3_9") (pintype "open_collector"))
      (node (ref "N6") (pin "3") (pinfunction "3_3") (pintype "bidirectional"))
    )
    (net (code "124") (name "Net-(IC11A-4)") (class "Default")
      (node (ref "IC11") (pin "13") (pinfunction "4_13") (pintype "open_collector"))
      (node (ref "N6") (pin "4") (pinfunction "4_4") (pintype "bidirectional"))
    )
    (net (code "125") (name "Net-(IC11A-5)") (class "Default")
      (node (ref "IC11") (pin "14") (pinfunction "5_14") (pintype "open_collector"))
      (node (ref "N6") (pin "5") (pinfunction "5_5") (pintype "bidirectional"))
    )
    (net (code "126") (name "Net-(IC11A-6)") (class "Default")
      (node (ref "IC11") (pin "11") (pinfunction "6_11") (pintype "open_collector"))
      (node (ref "N6") (pin "6") (pinfunction "6_6") (pintype "bidirectional"))
    )
    (net (code "127") (name "Net-(IC11A-7)") (class "Default")
      (node (ref "IC11") (pin "10") (pinfunction "7_10") (pintype "open_collector"))
      (node (ref "N6") (pin "7") (pinfunction "7_7") (pintype "bidirectional"))
    )
    (net (code "128") (name "Net-(IC11A-8)") (class "Default")
      (node (ref "IC11") (pin "1") (pinfunction "8_1") (pintype "open_collector"))
      (node (ref "N6") (pin "8") (pinfunction "8_8") (pintype "bidirectional"))
    )
    (net (code "129") (name "Net-(IC11A-9)") (class "Default")
      (node (ref "IC11") (pin "2") (pinfunction "9_2") (pintype "open_collector"))
      (node (ref "N6") (pin "9") (pinfunction "9_9") (pintype "bidirectional"))
    )
    (net (code "130") (name "Net-(IC12A-QH*)") (class "Default")
      (node (ref "IC12") (pin "9") (pinfunction "QH*_9") (pintype "tri_state"))
      (node (ref "IC13") (pin "14") (pinfunction "SER_14") (pintype "input"))
    )
    (net (code "131") (name "Net-(N1-PadA)") (class "Default")
      (node (ref "N1") (pin "A") (pinfunction "A_A") (pintype "bidirectional"))
      (node (ref "R5") (pin "1") (pinfunction "1_1") (pintype "passive"))
    )
    (net (code "132") (name "Net-(N1-PadLHDP)") (class "Default")
      (node (ref "N1") (pin "LHDP") (pinfunction "LHDP_LHDP") (pintype "bidirectional"))
      (node (ref "R1") (pin "2") (pinfunction "2_2") (pintype "passive"))
    )
    (net (code "133") (name "Net-(N1-PadRHDP)") (class "Default")
      (node (ref "N1") (pin "RHDP") (pinfunction "RHDP_RHDP") (pintype "bidirectional"))
      (node (ref "R7") (pin "2") (pinfunction "2_2") (pintype "passive"))
    )
    (net (code "134") (name "Net-(N2-PadA)") (class "Default")
      (node (ref "N2") (pin "A") (pinfunction "A_A") (pintype "bidirectional"))
      (node (ref "R12") (pin "1") (pinfunction "1_1") (pintype "passive"))
    )
    (net (code "135") (name "Net-(N2-PadLHDP)") (class "Default")
      (node (ref "N2") (pin "LHDP") (pinfunction "LHDP_LHDP") (pintype "bidirectional"))
      (node (ref "R8") (pin "2") (pinfunction "2_2") (pintype "passive"))
    )
    (net (code "136") (name "Net-(N2-PadRHDP)") (class "Default")
      (node (ref "N2") (pin "RHDP") (pinfunction "RHDP_RHDP") (pintype "bidirectional"))
      (node (ref "R14") (pin "2") (pinfunction "2_2") (pintype "passive"))
    )
    (net (code "137") (name "Net-(N3-PadA)") (class "Default")
      (node (ref "N3") (pin "A") (pinfunction "A_A") (pintype "bidirectional"))
      (node (ref "R19") (pin "1") (pinfunction "1_1") (pintype "passive"))
    )
    (net (code "138") (name "Net-(N3-PadLHDP)") (class "Default")
      (node (ref "N3") (pin "LHDP") (pinfunction "LHDP_LHDP") (pintype "bidirectional"))
      (node (ref "R15") (pin "2") (pinfunction "2_2") (pintype "passive"))
    )
    (net (code "139") (name "Net-(N3-PadRHDP)") (class "Default")
      (node (ref "N3") (pin "RHDP") (pinfunction "RHDP_RHDP") (pintype "bidirectional"))
      (node (ref "R21") (pin "2") (pinfunction "2_2") (pintype "passive"))
    )
    (net (code "140") (name "Net-(N4-PadA)") (class "Default")
      (node (ref "N4") (pin "A") (pinfunction "A_A") (pintype "bidirectional"))
      (node (ref "R27") (pin "1") (pinfunction "1_1") (pintype "passive"))
    )
    (net (code "141") (name "Net-(N4-PadLHDP)") (class "Default")
      (node (ref "N4") (pin "LHDP") (pinfunction "LHDP_LHDP") (pintype "bidirectional"))
      (node (ref "R22") (pin "2") (pinfunction "2_2") (pintype "passive"))
    )
    (net (code "142") (name "Net-(N4-PadRHDP)") (class "Default")
      (node (ref "N4") (pin "RHDP") (pinfunction "RHDP_RHDP") (pintype "bidirectional"))
      (node (ref "R30") (pin "2") (pinfunction "2_2") (pintype "passive"))
    )
    (net (code "143") (name "Net-(N5-PadA)") (class "Default")
      (node (ref "N5") (pin "A") (pinfunction "A_A") (pintype "bidirectional"))
      (node (ref "R35") (pin "1") (pinfunction "1_1") (pintype "passive"))
    )
    (net (code "144") (name "Net-(N5-PadLHDP)") (class "Default")
      (node (ref "N5") (pin "LHDP") (pinfunction "LHDP_LHDP") (pintype "bidirectional"))
      (node (ref "R31") (pin "2") (pinfunction "2_2") (pintype "passive"))
    )
    (net (code "145") (name "Net-(N5-PadRHDP)") (class "Default")
      (node (ref "N5") (pin "RHDP") (pinfunction "RHDP_RHDP") (pintype "bidirectional"))
      (node (ref "R37") (pin "2") (pinfunction "2_2") (pintype "passive"))
    )
    (net (code "146") (name "Net-(N6-PadA)") (class "Default")
      (node (ref "N6") (pin "A") (pinfunction "A_A") (pintype "bidirectional"))
      (node (ref "R42") (pin "1") (pinfunction "1_1") (pintype "passive"))
    )
    (net (code "147") (name "Net-(N6-PadLHDP)") (class "Default")
      (node (ref "N6") (pin "LHDP") (pinfunction "LHDP_LHDP") (pintype "bidirectional"))
      (node (ref "R38") (pin "2") (pinfunction "2_2") (pintype "passive"))
    )
    (net (code "148") (name "Net-(N6-PadRHDP)") (class "Default")
      (node (ref "N6") (pin "RHDP") (pinfunction "RHDP_RHDP") (pintype "bidirectional"))
      (node (ref "R44") (pin "2") (pinfunction "2_2") (pintype "passive"))
    )
    (net (code "149") (name "Net-(N7-PadA)") (class "Default")
      (node (ref "N7") (pin "A") (pinfunction "A_A") (pintype "bidirectional"))
      (node (ref "R46") (pin "A") (pinfunction "A_A") (pintype "passive"))
    )
    (net (code "150") (name "Net-(N7-PadK)") (class "Default")
      (node (ref "N7") (pin "K") (pinfunction "K_K") (pintype "bidirectional"))
      (node (ref "T25") (pin "C") (pinfunction "C_C") (pintype "passive"))
    )
    (net (code "151") (name "Net-(N8-PadA)") (class "Default")
      (node (ref "N8") (pin "A") (pinfunction "A_A") (pintype "bidirectional"))
      (node (ref "R50") (pin "A") (pinfunction "A_A") (pintype "passive"))
    )
    (net (code "152") (name "Net-(N8-PadK)") (class "Default")
      (node (ref "N8") (pin "K") (pinfunction "K_K") (pintype "bidirectional"))
      (node (ref "T26") (pin "C") (pinfunction "C_C") (pintype "passive"))
    )
    (net (code "153") (name "Net-(R1-Pad3)") (class "Default")
      (node (ref "R1") (pin "3") (pinfunction "3_3") (pintype "passive"))
      (node (ref "T2") (pin "C") (pinfunction "C_C") (pintype "passive"))
    )
    (net (code "154") (name "Net-(R2-Pad1)") (class "Default")
      (node (ref "R2") (pin "1") (pinfunction "1_1") (pintype "passive"))
      (node (ref "T1") (pin "C") (pinfunction "C_C") (pintype "passive"))
      (node (ref "T3") (pin "B") (pinfunction "B_B") (pintype "passive"))
    )
    (net (code "155") (name "Net-(R3-Pad2)") (class "Default")
      (node (ref "R3") (pin "2") (pinfunction "2_2") (pintype "passive"))
      (node (ref "T1") (pin "E") (pinfunction "E_E") (pintype "passive"))
    )
    (net (code "156") (name "Net-(R4-Pad2)") (class "Default")
      (node (ref "R4") (pin "2") (pinfunction "2_2") (pintype "passive"))
      (node (ref "T2") (pin "B") (pinfunction "B_B") (pintype "passive"))
    )
    (net (code "157") (name "Net-(R5-Pad2)") (class "Default")
      (node (ref "R5") (pin "2") (pinfunction "2_2") (pintype "passive"))
      (node (ref "T3") (pin "C") (pinfunction "C_C") (pintype "passive"))
    )
    (net (code "158") (name "Net-(R6-Pad2)") (class "Default")
      (node (ref "R6") (pin "2") (pinfunction "2_2") (pintype "passive"))
      (node (ref "T4") (pin "B") (pinfunction "B_B") (pintype "passive"))
    )
    (net (code "159") (name "Net-(R7-Pad1)") (class "Default")
      (node (ref "R7") (pin "1") (pinfunction "1_1") (pintype "passive"))
      (node (ref "T4") (pin "C") (pinfunction "C_C") (pintype "passive"))
    )
    (net (code "160") (name "Net-(R8-Pad3)") (class "Default")
      (node (ref "R8") (pin "3") (pinfunction "3_3") (pintype "passive"))
      (node (ref "T6") (pin "C") (pinfunction "C_C") (pintype "passive"))
    )
    (net (code "161") (name "Net-(R9-Pad1)") (class "Default")
      (node (ref "R9") (pin "1") (pinfunction "1_1") (pintype "passive"))
      (node (ref "T5") (pin "C") (pinfunction "C_C") (pintype "passive"))
      (node (ref "T7") (pin "B") (pinfunction "B_B") (pintype "passive"))
    )
    (net (code "162") (name "Net-(R10-Pad2)") (class "Default")
      (node (ref "R10") (pin "2") (pinfunction "2_2") (pintype "passive"))
      (node (ref "T5") (pin "E") (pinfunction "E_E") (pintype "passive"))
    )
    (net (code "163") (name "Net-(R11-Pad2)") (class "Default")
      (node (ref "R11") (pin "2") (pinfunction "2_2") (pintype "passive"))
      (node (ref "T6") (pin "B") (pinfunction "B_B") (pintype "passive"))
    )
    (net (code "164") (name "Net-(R12-Pad2)") (class "Default")
      (node (ref "R12") (pin "2") (pinfunction "2_2") (pintype "passive"))
      (node (ref "T7") (pin "C") (pinfunction "C_C") (pintype "passive"))
    )
    (net (code "165") (name "Net-(R13-Pad2)") (class "Default")
      (node (ref "R13") (pin "2") (pinfunction "2_2") (pintype "passive"))
      (node (ref "T8") (pin "B") (pinfunction "B_B") (pintype "passive"))
    )
    (net (code "166") (name "Net-(R14-Pad1)") (class "Default")
      (node (ref "R14") (pin "1") (pinfunction "1_1") (pintype "passive"))
      (node (ref "T8") (pin "C") (pinfunction "C_C") (pintype "passive"))
    )
    (net (code "167") (name "Net-(R15-Pad3)") (class "Default")
      (node (ref "R15") (pin "3") (pinfunction "3_3") (pintype "passive"))
      (node (ref "T10") (pin "C") (pinfunction "C_C") (pintype "passive"))
    )
    (net (code "168") (name "Net-(R16-Pad1)") (class "Default")
      (node (ref "R16") (pin "1") (pinfunction "1_1") (pintype "passive"))
      (node (ref "T11") (pin "B") (pinfunction "B_B") (pintype "passive"))
      (node (ref "T9") (pin "C") (pinfunction "C_C") (pintype "passive"))
    )
    (net (code "169") (name "Net-(R17-Pad2)") (class "Default")
      (node (ref "R17") (pin "2") (pinfunction "2_2") (pintype "passive"))
      (node (ref "T9") (pin "E") (pinfunction "E_E") (pintype "passive"))
    )
    (net (code "170") (name "Net-(R18-Pad2)") (class "Default")
      (node (ref "R18") (pin "2") (pinfunction "2_2") (pintype "passive"))
      (node (ref "T10") (pin "B") (pinfunction "B_B") (pintype "passive"))
    )
    (net (code "171") (name "Net-(R19-Pad2)") (class "Default")
      (node (ref "R19") (pin "2") (pinfunction "2_2") (pintype "passive"))
      (node (ref "T11") (pin "C") (pinfunction "C_C") (pintype "passive"))
    )
    (net (code "172") (name "Net-(R20-Pad2)") (class "Default")
      (node (ref "R20") (pin "2") (pinfunction "2_2") (pintype "passive"))
      (node (ref "T12") (pin "B") (pinfunction "B_B") (pintype "passive"))
    )
    (net (code "173") (name "Net-(R21-Pad1)") (class "Default")
      (node (ref "R21") (pin "1") (pinfunction "1_1") (pintype "passive"))
      (node (ref "T12") (pin "C") (pinfunction "C_C") (pintype "passive"))
    )
    (net (code "174") (name "Net-(R22-Pad3)") (class "Default")
      (node (ref "R22") (pin "3") (pinfunction "3_3") (pintype "passive"))
      (node (ref "T14") (pin "C") (pinfunction "C_C") (pintype "passive"))
    )
    (net (code "175") (name "Net-(R23-Pad1)") (class "Default")
      (node (ref "R23") (pin "1") (pinfunction "1_1") (pintype "passive"))
      (node (ref "T13") (pin "C") (pinfunction "C_C") (pintype "passive"))
      (node (ref "T15") (pin "B") (pinfunction "B_B") (pintype "passive"))
    )
    (net (code "176") (name "Net-(R24-Pad2)") (class "Default")
      (node (ref "R24") (pin "2") (pinfunction "2_2") (pintype "passive"))
      (node (ref "T13") (pin "E") (pinfunction "E_E") (pintype "passive"))
    )
    (net (code "177") (name "Net-(R25-Pad2)") (class "Default")
      (node (ref "R25") (pin "2") (pinfunction "2_2") (pintype "passive"))
      (node (ref "T14") (pin "B") (pinfunction "B_B") (pintype "passive"))
    )
    (net (code "178") (name "Net-(R27-Pad2)") (class "Default")
      (node (ref "R27") (pin "2") (pinfunction "2_2") (pintype "passive"))
      (node (ref "T15") (pin "C") (pinfunction "C_C") (pintype "passive"))
    )
    (net (code "179") (name "Net-(R29-Pad2)") (class "Default")
      (node (ref "R29") (pin "2") (pinfunction "2_2") (pintype "passive"))
      (node (ref "T16") (pin "B") (pinfunction "B_B") (pintype "passive"))
    )
    (net (code "180") (name "Net-(R30-Pad1)") (class "Default")
      (node (ref "R30") (pin "1") (pinfunction "1_1") (pintype "passive"))
      (node (ref "T16") (pin "C") (pinfunction "C_C") (pintype "passive"))
    )
    (net (code "181") (name "Net-(R31-Pad3)") (class "Default")
      (node (ref "R31") (pin "3") (pinfunction "3_3") (pintype "passive"))
      (node (ref "T18") (pin "C") (pinfunction "C_C") (pintype "passive"))
    )
    (net (code "182") (name "Net-(R32-Pad1)") (class "Default")
      (node (ref "R32") (pin "1") (pinfunction "1_1") (pintype "passive"))
      (node (ref "T17") (pin "C") (pinfunction "C_C") (pintype "passive"))
      (node (ref "T19") (pin "B") (pinfunction "B_B") (pintype "passive"))
    )
    (net (code "183") (name "Net-(R33-Pad2)") (class "Default")
      (node (ref "R33") (pin "2") (pinfunction "2_2") (pintype "passive"))
      (node (ref "T17") (pin "E") (pinfunction "E_E") (pintype "passive"))
    )
    (net (code "184") (name "Net-(R34-Pad2)") (class "Default")
      (node (ref "R34") (pin "2") (pinfunction "2_2") (pintype "passive"))
      (node (ref "T18") (pin "B") (pinfunction "B_B") (pintype "passive"))
    )
    (net (code "185") (name "Net-(R35-Pad2)") (class "Default")
      (node (ref "R35") (pin "2") (pinfunction "2_2") (pintype "passive"))
      (node (ref "T19") (pin "C") (pinfunction "C_C") (pintype "passive"))
    )
    (net (code "186") (name "Net-(R36-Pad2)") (class "Default")
      (node (ref "R36") (pin "2") (pinfunction "2_2") (pintype "passive"))
      (node (ref "T20") (pin "B") (pinfunction "B_B") (pintype "passive"))
    )
    (net (code "187") (name "Net-(R37-Pad1)") (class "Default")
      (node (ref "R37") (pin "1") (pinfunction "1_1") (pintype "passive"))
      (node (ref "T20") (pin "C") (pinfunction "C_C") (pintype "passive"))
    )
    (net (code "188") (name "Net-(R38-Pad3)") (class "Default")
      (node (ref "R38") (pin "3") (pinfunction "3_3") (pintype "passive"))
      (node (ref "T22") (pin "C") (pinfunction "C_C") (pintype "passive"))
    )
    (net (code "189") (name "Net-(R39-Pad1)") (class "Default")
      (node (ref "R39") (pin "1") (pinfunction "1_1") (pintype "passive"))
      (node (ref "T21") (pin "C") (pinfunction "C_C") (pintype "passive"))
      (node (ref "T23") (pin "B") (pinfunction "B_B") (pintype "passive"))
    )
    (net (code "190") (name "Net-(R40-Pad2)") (class "Default")
      (node (ref "R40") (pin "2") (pinfunction "2_2") (pintype "passive"))
      (node (ref "T21") (pin "E") (pinfunction "E_E") (pintype "passive"))
    )
    (net (code "191") (name "Net-(R41-Pad2)") (class "Default")
      (node (ref "R41") (pin "2") (pinfunction "2_2") (pintype "passive"))
      (node (ref "T22") (pin "B") (pinfunction "B_B") (pintype "passive"))
    )
    (net (code "192") (name "Net-(R42-Pad2)") (class "Default")
      (node (ref "R42") (pin "2") (pinfunction "2_2") (pintype "passive"))
      (node (ref "T23") (pin "C") (pinfunction "C_C") (pintype "passive"))
    )
    (net (code "193") (name "Net-(R43-Pad2)") (class "Default")
      (node (ref "R43") (pin "2") (pinfunction "2_2") (pintype "passive"))
      (node (ref "T24") (pin "B") (pinfunction "B_B") (pintype "passive"))
    )
    (net (code "194") (name "Net-(R44-Pad1)") (class "Default")
      (node (ref "R44") (pin "1") (pinfunction "1_1") (pintype "passive"))
      (node (ref "T24") (pin "C") (pinfunction "C_C") (pintype "passive"))
    )
    (net (code "195") (name "Net-(R45-Pad1)") (class "Default")
      (node (ref "R45") (pin "1") (pinfunction "1_1") (pintype "passive"))
      (node (ref "T25") (pin "B") (pinfunction "B_B") (pintype "passive"))
    )
    (net (code "196") (name "Net-(R46-PadS)") (class "Default")
      (node (ref "R46") (pin "S") (pinfunction "S_S") (pintype "passive"))
      (node (ref "R47") (pin "A") (pinfunction "A_A") (pintype "passive"))
    )
    (net (code "197") (name "Net-(R48-Pad1)") (class "Default")
      (node (ref "R48") (pin "1") (pinfunction "1_1") (pintype "passive"))
      (node (ref "T26") (pin "B") (pinfunction "B_B") (pintype "passive"))
    )
    (net (code "198") (name "Net-(R50-PadS)") (class "Default")
      (node (ref "R50") (pin "S") (pinfunction "S_S") (pintype "passive"))
      (node (ref "R51") (pin "A") (pinfunction "A_A") (pintype "passive"))
    )
    (net (code "199") (name "unconnected-(IC7-SQW-Pad7)") (class "Default")
      (node (ref "IC7") (pin "7") (pinfunction "SQW_7") (pintype "open_collector"))
    )
    (net (code "200") (name "unconnected-(IC13A-QF-Pad5)") (class "Default")
      (node (ref "IC13") (pin "5") (pinfunction "QF_5") (pintype "tri_state"))
    )
    (net (code "201") (name "unconnected-(IC13A-QG-Pad6)") (class "Default")
      (node (ref "IC13") (pin "6") (pinfunction "QG_6") (pintype "tri_state"))
    )
    (net (code "202") (name "unconnected-(IC13A-QH*-Pad9)") (class "Default")
      (node (ref "IC13") (pin "9") (pinfunction "QH*_9") (pintype "tri_state"))
    )
    (net (code "203") (name "unconnected-(IC13A-QH-Pad7)") (class "Default")
      (node (ref "IC13") (pin "7") (pinfunction "QH_7") (pintype "tri_state"))
    )
    (net (code "204") (name "unconnected-(R1-Pad1)") (class "Default")
      (node (ref "R1") (pin "1") (pinfunction "1_1") (pintype "passive"))
    )
    (net (code "205") (name "unconnected-(R7-Pad3)") (class "Default")
      (node (ref "R7") (pin "3") (pinfunction "3_3") (pintype "passive"))
    )
    (net (code "206") (name "unconnected-(R8-Pad1)") (class "Default")
      (node (ref "R8") (pin "1") (pinfunction "1_1") (pintype "passive"))
    )
    (net (code "207") (name "unconnected-(R14-Pad3)") (class "Default")
      (node (ref "R14") (pin "3") (pinfunction "3_3") (pintype "passive"))
    )
    (net (code "208") (name "unconnected-(R15-Pad1)") (class "Default")
      (node (ref "R15") (pin "1") (pinfunction "1_1") (pintype "passive"))
    )
    (net (code "209") (name "unconnected-(R21-Pad3)") (class "Default")
      (node (ref "R21") (pin "3") (pinfunction "3_3") (pintype "passive"))
    )
    (net (code "210") (name "unconnected-(R22-Pad1)") (class "Default")
      (node (ref "R22") (pin "1") (pinfunction "1_1") (pintype "passive"))
    )
    (net (code "211") (name "unconnected-(R30-Pad3)") (class "Default")
      (node (ref "R30") (pin "3") (pinfunction "3_3") (pintype "passive"))
    )
    (net (code "212") (name "unconnected-(R31-Pad1)") (class "Default")
      (node (ref "R31") (pin "1") (pinfunction "1_1") (pintype "passive"))
    )
    (net (code "213") (name "unconnected-(R37-Pad3)") (class "Default")
      (node (ref "R37") (pin "3") (pinfunction "3_3") (pintype "passive"))
    )
    (net (code "214") (name "unconnected-(R38-Pad1)") (class "Default")
      (node (ref "R38") (pin "1") (pinfunction "1_1") (pintype "passive"))
    )
    (net (code "215") (name "unconnected-(R44-Pad3)") (class "Default")
      (node (ref "R44") (pin "3") (pinfunction "3_3") (pintype "passive"))
    )
    (net (code "216") (name "unconnected-(R46-PadE)") (class "Default")
      (node (ref "R46") (pin "E") (pinfunction "E_E") (pintype "passive"))
    )
    (net (code "217") (name "unconnected-(R47-PadE)") (class "Default")
      (node (ref "R47") (pin "E") (pinfunction "E_E") (pintype "passive"))
    )
    (net (code "218") (name "unconnected-(R49-PadA)") (class "Default")
      (node (ref "R49") (pin "A") (pinfunction "A_A") (pintype "passive"))
    )
    (net (code "219") (name "unconnected-(R50-PadE)") (class "Default")
      (node (ref "R50") (pin "E") (pinfunction "E_E") (pintype "passive"))
    )
    (net (code "220") (name "unconnected-(R51-PadE)") (class "Default")
      (node (ref "R51") (pin "E") (pinfunction "E_E") (pintype "passive"))
    )
    (net (code "221") (name "unconnected-(SV1-Pad1)") (class "Default")
      (node (ref "SV1") (pin "1") (pinfunction "1_1") (pintype "passive"))
    )
    (net (code "222") (name "unconnected-(SV1-Pad2)") (class "Default")
      (node (ref "SV1") (pin "2") (pinfunction "2_2") (pintype "passive"))
    )
    (net (code "223") (name "unconnected-(SV3-Pad1)") (class "Default")
      (node (ref "SV3") (pin "1") (pinfunction "1_1") (pintype "passive"))
    )
    (net (code "224") (name "unconnected-(SV3-Pad2)") (class "Default")
      (node (ref "SV3") (pin "2") (pinfunction "2_2") (pintype "passive"))
    )
    (net (code "225") (name "unconnected-(SV3-Pad3)") (class "Default")
      (node (ref "SV3") (pin "3") (pinfunction "3_3") (pintype "passive"))
    )
    (net (code "226") (name "unconnected-(SV8-Pad1)") (class "Default")
      (node (ref "SV8") (pin "1") (pinfunction "1_1") (pintype "passive"))
    )
    (net (code "227") (name "unconnected-(SV8-Pad2)") (class "Default")
      (node (ref "SV8") (pin "2") (pinfunction "2_2") (pintype "passive"))
    )
  )
)
